# Part1.net
KiCad netlist of a schematic drawn in Altium Designer
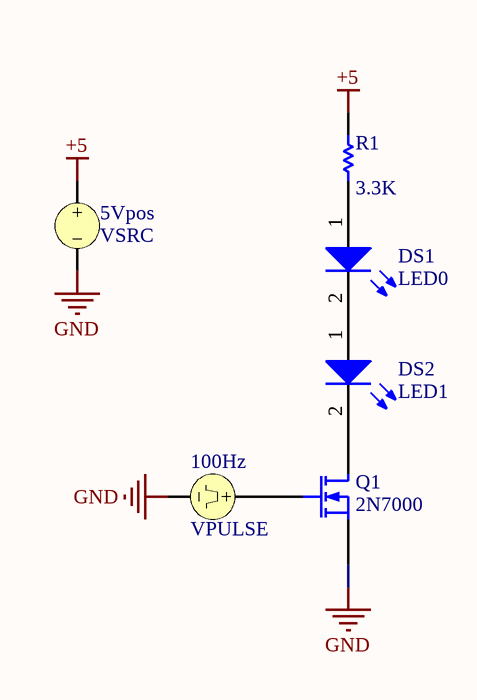
[diagram p0: Part1.SchDoc]

(export (version "E")
  (design (tool "Eeschema 10.0.6"))
  (components
    (comp (ref "5Vpos")
      (value "VSRC")
      (description "Voltage Source")
      (fields (field (name "PUBLISHER") "Altium Limited"))
      (libsource (lib "Simulation Sources") (part "VSRC"))
    )
    (comp (ref "100Hz")
      (value "VPULSE")
      (description "Pulse Voltage Source")
      (fields (field (name "PUBLISHER") "Altium Limited"))
      (libsource (lib "Simulation Sources") (part "VPULSE"))
    )
    (comp (ref "DS1")
      (value "LED0")
      (footprint "LED-0")
      (description "Typical INFRARED GaAs LED")
      (fields
        (field (name "MANUFACTURER") "Generic Components")
        (field (name "PUBLISHER") "Altium Hobart Technology Centre")
      )
      (libsource (lib "ME218_BaseLib") (part "LED0"))
    )
    (comp (ref "DS2")
      (value "LED1")
      (footprint "LED-1")
      (description "Typical RED GaAs LED")
      (fields
        (field (name "MANUFACTURER") "Generic Components")
        (field (name "PUBLISHER") "Altium Hobart Technology Centre")
      )
      (libsource (lib "ME218_BaseLib") (part "LED1"))
    )
    (comp (ref "Q1")
      (value "2N7000")
      (footprint "BCY-W3/D5")
      (description "N-Channel Enhancement Mode Vertical DMOS FET")
      (fields
        (field (name "MANUFACTURER") "Zetex")
        (field (name "PUBLISHER") "Altium Hobart Technology Centre")
      )
      (libsource (lib "ME218_BaseLib") (part "2N7000"))
    )
    (comp (ref "R1")
      (value "3.3K")
      (footprint "AXIAL-0.3")
      (description "Resistor")
      (fields
        (field (name "MANUFACTURER") "Generic Components")
        (field (name "Comment") "3.3k")
        (field (name "PUBLISHER") "Altium Hobart Technology Centre")
      )
      (libsource (lib "ME218_BaseLib") (part "Res1"))
    )
  )
  (nets
    (net (code "1") (name "+5") (class "Default")
      (node (ref "5Vpos") (pin "1") (pinfunction "1_1") (pintype "passive"))
      (node (ref "R1") (pin "2") (pinfunction "2_2") (pintype "passive"))
    )
    (net (code "2") (name "GND") (class "Default")
      (node (ref "100Hz") (pin "2") (pinfunction "2_2") (pintype "passive"))
      (node (ref "5Vpos") (pin "2") (pinfunction "2_2") (pintype "passive"))
      (node (ref "Q1") (pin "1") (pinfunction "S_1") (pintype "passive"))
    )
    (net (code "3") (name "Net-(DS1-A)") (class "Default")
      (node (ref "DS1") (pin "1") (pinfunction "A_1") (pintype "passive"))
      (node (ref "R1") (pin "1") (pinfunction "1_1") (pintype "passive"))
    )
    (net (code "4") (name "Net-(DS1-K)") (class "Default")
      (node (ref "DS1") (pin "2") (pinfunction "K_2") (pintype "passive"))
      (node (ref "DS2") (pin "1") (pinfunction "A_1") (pintype "passive"))
    )
    (net (code "5") (name "Net-(DS2-K)") (class "Default")
      (node (ref "DS2") (pin "2") (pinfunction "K_2") (pintype "passive"))
      (node (ref "Q1") (pin "3") (pinfunction "D_3") (pintype "passive"))
    )
    (net (code "6") (name "Net-(Q1-G)") (class "Default")
      (node (ref "100Hz") (pin "1") (pinfunction "1_1") (pintype "passive"))
      (node (ref "Q1") (pin "2") (pinfunction "G_2") (pintype "passive"))
    )
  )
)
